# KickerBoard.net
KiCad netlist of a schematic drawn in EAGLE
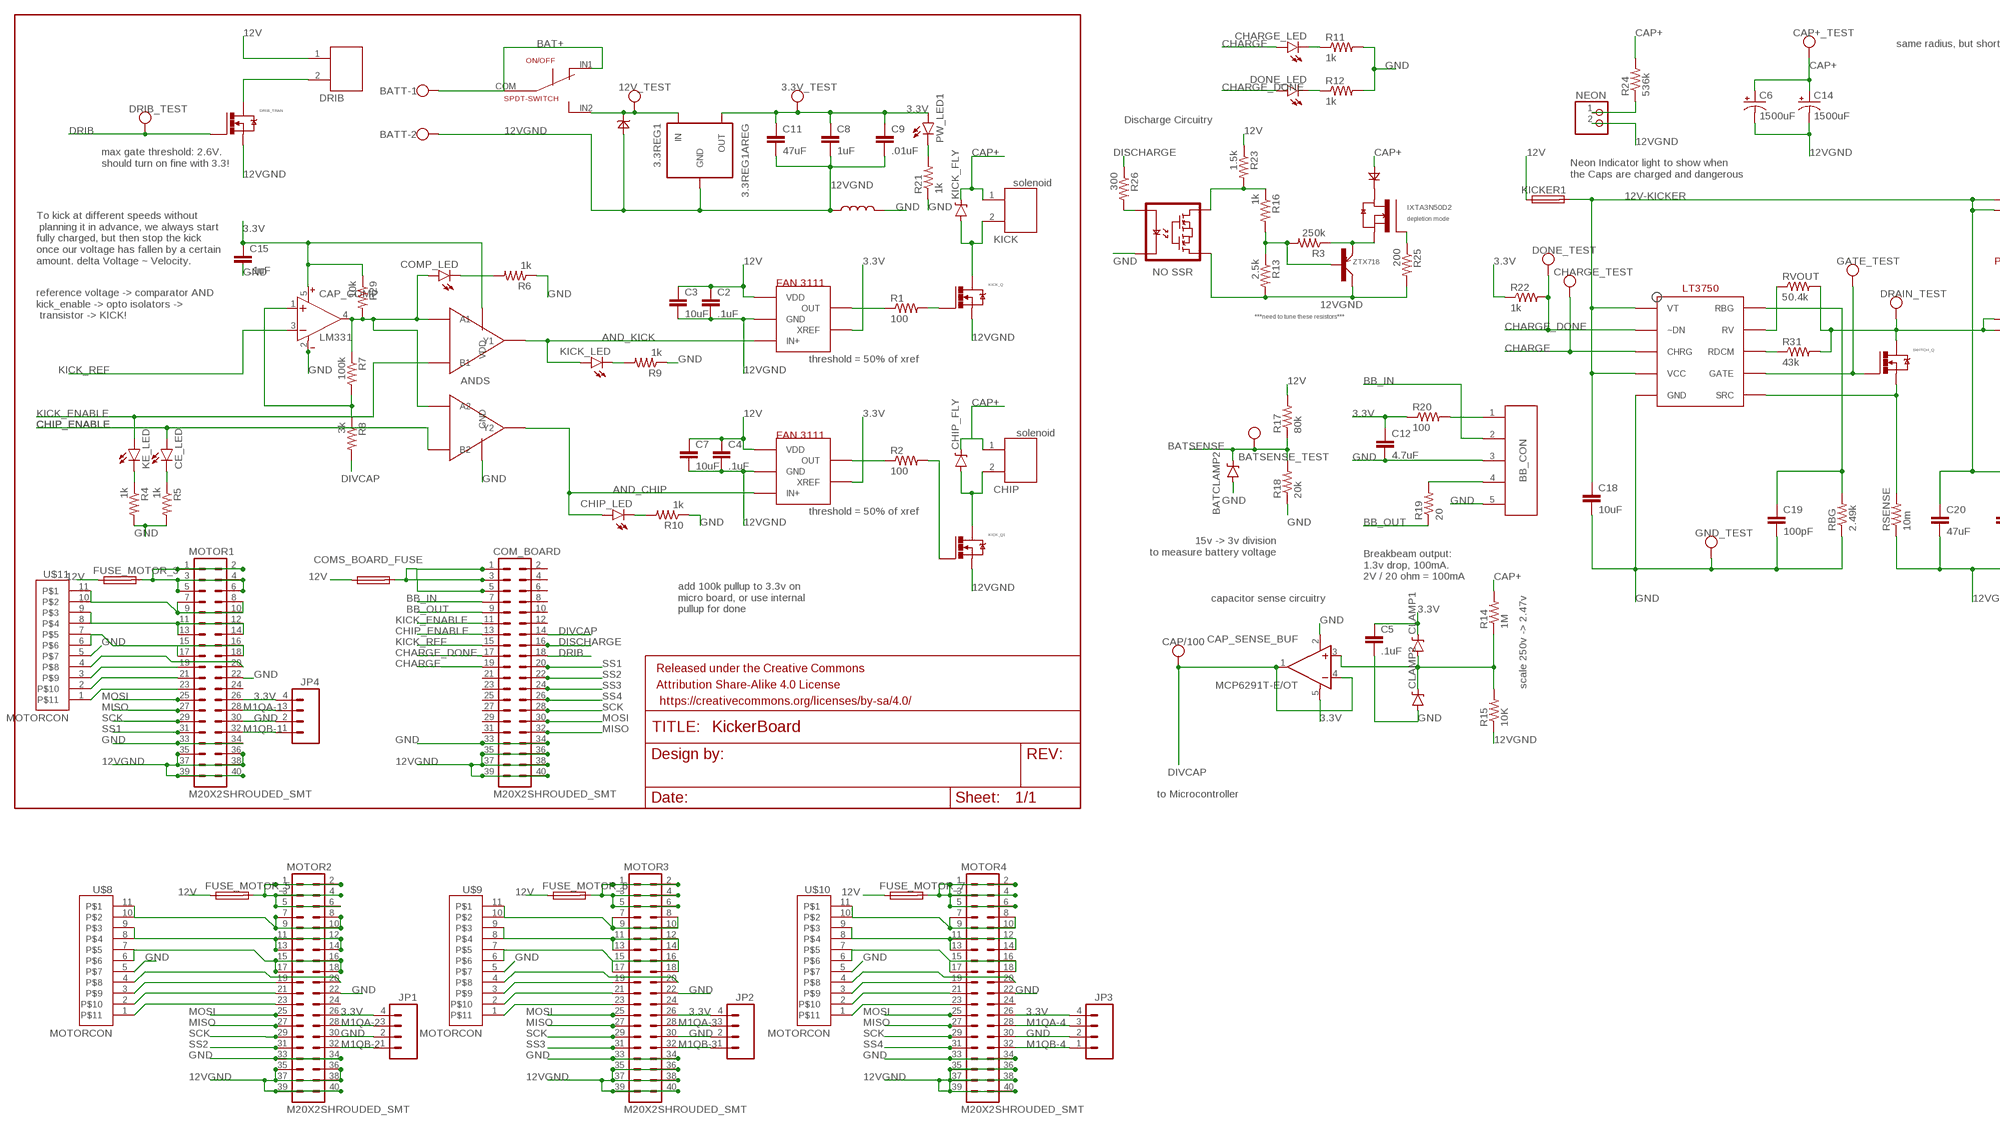
[diagram p0: schematic, sheet 1, part 1 of 3]
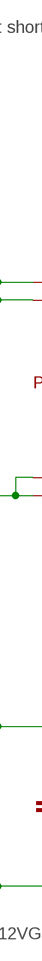
[diagram p1: schematic, sheet 1, part 2 of 3]
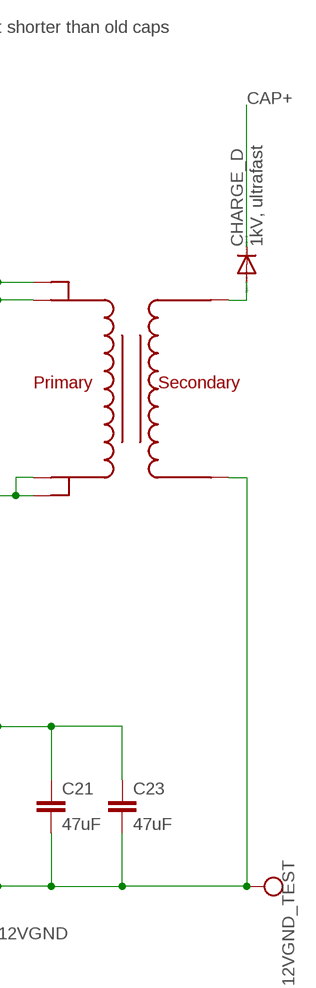
[diagram p2: schematic, sheet 1, part 3 of 3]

(export (version "E")
  (design (tool "Eeschema 10.0.6"))
  (components
    (comp (ref "3.3REG1")
      (value "3.3REG1AREG")
      (footprint "eagle-import:DPAK")
      (libsource (lib "eagle-import") (part "3.3REG1AREG"))
    )
    (comp (ref "3.3V_TEST")
      (value "TEST_PT")
      (footprint "eagle-import:TESTING_PT")
      (libsource (lib "eagle-import") (part "TEST_PT"))
    )
    (comp (ref "12VGND_TEST")
      (value "TEST_PT")
      (footprint "eagle-import:TESTING_PT")
      (libsource (lib "eagle-import") (part "TEST_PT"))
    )
    (comp (ref "12V_TEST")
      (value "TEST_PT")
      (footprint "eagle-import:TESTING_PT")
      (libsource (lib "eagle-import") (part "TEST_PT"))
    )
    (comp (ref "ANDS")
      (value "AND-DUAL")
      (footprint "eagle-import:TSSOP8")
      (libsource (lib "eagle-import") (part "AND-DUAL"))
    )
    (comp (ref "BATCLAMP2")
      (value "DIODE-ZENERDO214AC")
      (footprint "eagle-import:DO214AC")
      (libsource (lib "eagle-import") (part "DIODE-ZENERDO214AC"))
    )
    (comp (ref "BATSENSE_TEST")
      (value "TEST_PT")
      (footprint "eagle-import:TESTING_PT")
      (libsource (lib "eagle-import") (part "TEST_PT"))
    )
    (comp (ref "BATT")
      (value "W237-102")
      (footprint "eagle-import:W237-102")
      (fields (field (name "MPN") "237-102"))
      (libsource (lib "eagle-import") (part "W237-102"))
    )
    (comp (ref "BB_CON")
      (value "JST-5")
      (footprint "eagle-import:JST-5-2MM")
      (libsource (lib "eagle-import") (part "JST-5"))
    )
    (comp (ref "C2")
      (value ".1uF")
      (footprint "eagle-import:1206")
      (libsource (lib "eagle-import") (part "CAP1206"))
    )
    (comp (ref "C3")
      (value "10uF")
      (footprint "eagle-import:1206")
      (libsource (lib "eagle-import") (part "CAP1206"))
    )
    (comp (ref "C4")
      (value ".1uF")
      (footprint "eagle-import:1206")
      (libsource (lib "eagle-import") (part "CAP1206"))
    )
    (comp (ref "C5")
      (value ".1uF")
      (footprint "eagle-import:0805")
      (libsource (lib "eagle-import") (part "CAP0805"))
    )
    (comp (ref "C6")
      (value "1500uF")
      (footprint "eagle-import:EB35D")
      (libsource (lib "eagle-import") (part "CPOL-USE10-35"))
    )
    (comp (ref "C7")
      (value "10uF")
      (footprint "eagle-import:1206")
      (libsource (lib "eagle-import") (part "CAP1206"))
    )
    (comp (ref "C8")
      (value "1uF")
      (footprint "eagle-import:0805")
      (libsource (lib "eagle-import") (part "CAP0805"))
    )
    (comp (ref "C9")
      (value ".01uF")
      (footprint "eagle-import:0805")
      (libsource (lib "eagle-import") (part "CAP0805"))
    )
    (comp (ref "C11")
      (value "47uF")
      (footprint "eagle-import:1206")
      (libsource (lib "eagle-import") (part "CAP1206"))
    )
    (comp (ref "C12")
      (value "4.7uF")
      (footprint "eagle-import:0805")
      (libsource (lib "eagle-import") (part "CAP0805"))
    )
    (comp (ref "C14")
      (value "1500uF")
      (footprint "eagle-import:EB35D")
      (libsource (lib "eagle-import") (part "CPOL-USE10-35"))
    )
    (comp (ref "C15")
      (value ".1uF")
      (footprint "eagle-import:0805")
      (libsource (lib "eagle-import") (part "CAP0805"))
    )
    (comp (ref "C18")
      (value "10uF")
      (footprint "eagle-import:0805")
      (libsource (lib "eagle-import") (part "CAP0805"))
    )
    (comp (ref "C19")
      (value "100pF")
      (footprint "eagle-import:0805")
      (libsource (lib "eagle-import") (part "CAP0805"))
    )
    (comp (ref "C20")
      (value "47uF")
      (footprint "eagle-import:1206")
      (libsource (lib "eagle-import") (part "CAP1206"))
    )
    (comp (ref "C21")
      (value "47uF")
      (footprint "eagle-import:1206")
      (libsource (lib "eagle-import") (part "CAP1206"))
    )
    (comp (ref "C23")
      (value "47uF")
      (footprint "eagle-import:1206")
      (libsource (lib "eagle-import") (part "CAP1206"))
    )
    (comp (ref "CAP+_TEST")
      (value "TEST_PT")
      (footprint "eagle-import:TESTING_PT")
      (libsource (lib "eagle-import") (part "TEST_PT"))
    )
    (comp (ref "CAP/100")
      (value "TEST_PT")
      (footprint "eagle-import:TESTING_PT")
      (libsource (lib "eagle-import") (part "TEST_PT"))
    )
    (comp (ref "CAP_COMP")
      (value "LM331")
      (footprint "eagle-import:SOT23-5")
      (libsource (lib "eagle-import") (part "LM331"))
    )
    (comp (ref "CAP_SENSE_BUF")
      (value "MCP6291T-E/OT")
      (footprint "eagle-import:SOT23-5")
      (libsource (lib "eagle-import") (part "MCP6291T-E/OT"))
    )
    (comp (ref "CE_LED")
      (value "LED1206")
      (footprint "eagle-import:LED-1206")
      (libsource (lib "eagle-import") (part "LED1206"))
    )
    (comp (ref "CHARGE_D")
      (value "1kV, ultrafast")
      (footprint "eagle-import:DO214AC")
      (libsource (lib "eagle-import") (part "DIODE-DO214AC"))
    )
    (comp (ref "CHARGE_LED")
      (value "LED1206")
      (footprint "eagle-import:LED-1206")
      (libsource (lib "eagle-import") (part "LED1206"))
    )
    (comp (ref "CHARGE_TEST")
      (value "TEST_PT")
      (footprint "eagle-import:TESTING_PT")
      (libsource (lib "eagle-import") (part "TEST_PT"))
    )
    (comp (ref "CHARGE_U")
      (value "LT3750")
      (footprint "eagle-import:10-MSOP")
      (libsource (lib "eagle-import") (part "LT3750"))
    )
    (comp (ref "CHIP")
      (value "JST-22MM")
      (footprint "eagle-import:JST-2-2MM")
      (libsource (lib "eagle-import") (part "JST-22MM"))
    )
    (comp (ref "CHIP_FLY")
      (value "DIODE-ZENERDO214AB")
      (footprint "eagle-import:DO214AB")
      (libsource (lib "eagle-import") (part "DIODE-ZENERDO214AB"))
    )
    (comp (ref "CHIP_LED")
      (value "LED1206")
      (footprint "eagle-import:LED-1206")
      (libsource (lib "eagle-import") (part "LED1206"))
    )
    (comp (ref "CLAMP1")
      (value "DIODE-ZENERDO214AC")
      (footprint "eagle-import:DO214AC")
      (libsource (lib "eagle-import") (part "DIODE-ZENERDO214AC"))
    )
    (comp (ref "CLAMP2")
      (value "DIODE-ZENERDO214AC")
      (footprint "eagle-import:DO214AC")
      (libsource (lib "eagle-import") (part "DIODE-ZENERDO214AC"))
    )
    (comp (ref "COMP_LED")
      (value "LED1206")
      (footprint "eagle-import:LED-1206")
      (libsource (lib "eagle-import") (part "LED1206"))
    )
    (comp (ref "COMS_BOARD_FUSE")
      (value "TR5")
      (footprint "eagle-import:TR5")
      (libsource (lib "eagle-import") (part "TR5"))
    )
    (comp (ref "COM_BOARD")
      (value "M20X2SHROUDED_SMT")
      (footprint "eagle-import:2X20_SHROUDED_SMT")
      (libsource (lib "eagle-import") (part "M20X2SHROUDED_SMT"))
    )
    (comp (ref "DONE_LED")
      (value "LED1206")
      (footprint "eagle-import:LED-1206")
      (libsource (lib "eagle-import") (part "LED1206"))
    )
    (comp (ref "DONE_TEST")
      (value "TEST_PT")
      (footprint "eagle-import:TESTING_PT")
      (libsource (lib "eagle-import") (part "TEST_PT"))
    )
    (comp (ref "DRAIN_TEST")
      (value "TEST_PT")
      (footprint "eagle-import:TESTING_PT")
      (libsource (lib "eagle-import") (part "TEST_PT"))
    )
    (comp (ref "DRIB")
      (value "JST-22MM")
      (footprint "eagle-import:JST-2-2MM")
      (libsource (lib "eagle-import") (part "JST-22MM"))
    )
    (comp (ref "DRIB_TEST")
      (value "TEST_PT")
      (footprint "eagle-import:TESTING_PT")
      (libsource (lib "eagle-import") (part "TEST_PT"))
    )
    (comp (ref "DRIB_TRAN")
      (value "N-MOSFETDPAK")
      (footprint "eagle-import:DPAK")
      (libsource (lib "eagle-import") (part "N-MOSFETDPAK"))
    )
    (comp (ref "FRAME4")
      (value "FRAME-LETTER")
      (footprint "eagle-import:CREATIVE_COMMONS")
      (libsource (lib "eagle-import") (part "FRAME-LETTER"))
    )
    (comp (ref "FUSE_MOTOR_3")
      (value "TR5")
      (footprint "eagle-import:TR5")
      (libsource (lib "eagle-import") (part "TR5"))
    )
    (comp (ref "FUSE_MOTOR_5")
      (value "TR5")
      (footprint "eagle-import:TR5")
      (libsource (lib "eagle-import") (part "TR5"))
    )
    (comp (ref "FUSE_MOTOR_6")
      (value "TR5")
      (footprint "eagle-import:TR5")
      (libsource (lib "eagle-import") (part "TR5"))
    )
    (comp (ref "FUSE_MOTOR_7")
      (value "TR5")
      (footprint "eagle-import:TR5")
      (libsource (lib "eagle-import") (part "TR5"))
    )
    (comp (ref "GATE_TEST")
      (value "TEST_PT")
      (footprint "eagle-import:TESTING_PT")
      (libsource (lib "eagle-import") (part "TEST_PT"))
    )
    (comp (ref "GND_TEST")
      (value "TEST_PT")
      (footprint "eagle-import:TESTING_PT")
      (libsource (lib "eagle-import") (part "TEST_PT"))
    )
    (comp (ref "JP1")
      (value "M04SMD_RA_FEMALE")
      (footprint "eagle-import:1X04_SMD_RA_FEMALE")
      (libsource (lib "eagle-import") (part "M04SMD_RA_FEMALE"))
    )
    (comp (ref "JP2")
      (value "M04SMD_RA_FEMALE")
      (footprint "eagle-import:1X04_SMD_RA_FEMALE")
      (libsource (lib "eagle-import") (part "M04SMD_RA_FEMALE"))
    )
    (comp (ref "JP3")
      (value "M04SMD_RA_FEMALE")
      (footprint "eagle-import:1X04_SMD_RA_FEMALE")
      (libsource (lib "eagle-import") (part "M04SMD_RA_FEMALE"))
    )
    (comp (ref "JP4")
      (value "M04SMD_RA_FEMALE")
      (footprint "eagle-import:1X04_SMD_RA_FEMALE")
      (libsource (lib "eagle-import") (part "M04SMD_RA_FEMALE"))
    )
    (comp (ref "KE_LED")
      (value "LED1206")
      (footprint "eagle-import:LED-1206")
      (libsource (lib "eagle-import") (part "LED1206"))
    )
    (comp (ref "KICK")
      (value "JST-22MM")
      (footprint "eagle-import:JST-2-2MM")
      (libsource (lib "eagle-import") (part "JST-22MM"))
    )
    (comp (ref "KICKER1")
      (value "TR5")
      (footprint "eagle-import:TR5")
      (libsource (lib "eagle-import") (part "TR5"))
    )
    (comp (ref "KICK_FLY")
      (value "DIODE-ZENERDO214AB")
      (footprint "eagle-import:DO214AB")
      (libsource (lib "eagle-import") (part "DIODE-ZENERDO214AB"))
    )
    (comp (ref "KICK_LED")
      (value "LED1206")
      (footprint "eagle-import:LED-1206")
      (libsource (lib "eagle-import") (part "LED1206"))
    )
    (comp (ref "KICK_Q")
      (value "N-MOSFETDPAK")
      (footprint "eagle-import:DPAK")
      (libsource (lib "eagle-import") (part "N-MOSFETDPAK"))
    )
    (comp (ref "KICK_Q1")
      (value "N-MOSFETDPAK")
      (footprint "eagle-import:DPAK")
      (libsource (lib "eagle-import") (part "N-MOSFETDPAK"))
    )
    (comp (ref "MOTOR1")
      (value "M20X2SHROUDED_SMT")
      (footprint "eagle-import:2X20_SHROUDED_SMT")
      (libsource (lib "eagle-import") (part "M20X2SHROUDED_SMT"))
    )
    (comp (ref "MOTOR2")
      (value "M20X2SHROUDED_SMT")
      (footprint "eagle-import:2X20_SHROUDED_SMT")
      (libsource (lib "eagle-import") (part "M20X2SHROUDED_SMT"))
    )
    (comp (ref "MOTOR3")
      (value "M20X2SHROUDED_SMT")
      (footprint "eagle-import:2X20_SHROUDED_SMT")
      (libsource (lib "eagle-import") (part "M20X2SHROUDED_SMT"))
    )
    (comp (ref "MOTOR4")
      (value "M20X2SHROUDED_SMT")
      (footprint "eagle-import:2X20_SHROUDED_SMT")
      (libsource (lib "eagle-import") (part "M20X2SHROUDED_SMT"))
    )
    (comp (ref "NEON")
      (value "PINHD-1X2")
      (footprint "eagle-import:1X02")
      (libsource (lib "eagle-import") (part "PINHD-1X2"))
    )
    (comp (ref "ON/OFF")
      (value "SPDT-SWITCH")
      (footprint "eagle-import:CK_SWITCH")
      (libsource (lib "eagle-import") (part "SPDT-SWITCH"))
    )
    (comp (ref "PW_LED1")
      (value "LED1206")
      (footprint "eagle-import:LED-1206")
      (libsource (lib "eagle-import") (part "LED1206"))
    )
    (comp (ref "R1")
      (value "100")
      (footprint "eagle-import:0805")
      (libsource (lib "eagle-import") (part "SparkFun-Resistors_RESISTOR0805-RES"))
    )
    (comp (ref "R2")
      (value "100")
      (footprint "eagle-import:0805")
      (libsource (lib "eagle-import") (part "SparkFun-Resistors_RESISTOR0805-RES"))
    )
    (comp (ref "R3")
      (value "250k")
      (footprint "eagle-import:0805")
      (libsource (lib "eagle-import") (part "RESISTOR0805-RES"))
    )
    (comp (ref "R4")
      (value "1k")
      (footprint "eagle-import:0805")
      (libsource (lib "eagle-import") (part "RESISTOR0805-RES"))
    )
    (comp (ref "R5")
      (value "1k")
      (footprint "eagle-import:0805")
      (libsource (lib "eagle-import") (part "RESISTOR0805-RES"))
    )
    (comp (ref "R6")
      (value "1k")
      (footprint "eagle-import:0805")
      (libsource (lib "eagle-import") (part "RESISTOR0805-RES"))
    )
    (comp (ref "R7")
      (value "100k")
      (footprint "eagle-import:0805")
      (libsource (lib "eagle-import") (part "RESISTOR0805-RES"))
    )
    (comp (ref "R8")
      (value "3k")
      (footprint "eagle-import:0805")
      (libsource (lib "eagle-import") (part "RESISTOR0805-RES"))
    )
    (comp (ref "R9")
      (value "1k")
      (footprint "eagle-import:0805")
      (libsource (lib "eagle-import") (part "RESISTOR0805-RES"))
    )
    (comp (ref "R10")
      (value "1k")
      (footprint "eagle-import:0805")
      (libsource (lib "eagle-import") (part "RESISTOR0805-RES"))
    )
    (comp (ref "R11")
      (value "1k")
      (footprint "eagle-import:0805")
      (libsource (lib "eagle-import") (part "RESISTOR0805-RES"))
    )
    (comp (ref "R12")
      (value "1k")
      (footprint "eagle-import:0805")
      (libsource (lib "eagle-import") (part "RESISTOR0805-RES"))
    )
    (comp (ref "R13")
      (value "2.5k")
      (footprint "eagle-import:0805")
      (libsource (lib "eagle-import") (part "RESISTOR0805-RES"))
    )
    (comp (ref "R14")
      (value "1M")
      (footprint "eagle-import:0805")
      (libsource (lib "eagle-import") (part "SparkFun-Resistors_RESISTOR0805-RES"))
    )
    (comp (ref "R15")
      (value "10K")
      (footprint "eagle-import:0805")
      (libsource (lib "eagle-import") (part "SparkFun-Resistors_RESISTOR0805-RES"))
    )
    (comp (ref "R16")
      (value "1k")
      (footprint "eagle-import:0805")
      (libsource (lib "eagle-import") (part "RESISTOR0805-RES"))
    )
    (comp (ref "R17")
      (value "80k")
      (footprint "eagle-import:0805")
      (libsource (lib "eagle-import") (part "RESISTOR0805-RES"))
    )
    (comp (ref "R18")
      (value "20k")
      (footprint "eagle-import:0805")
      (libsource (lib "eagle-import") (part "RESISTOR0805-RES"))
    )
    (comp (ref "R19")
      (value "20")
      (footprint "eagle-import:0805")
      (libsource (lib "eagle-import") (part "RESISTOR0805-RES"))
    )
    (comp (ref "R20")
      (value "100")
      (footprint "eagle-import:0805")
      (libsource (lib "eagle-import") (part "RESISTOR0805-RES"))
    )
    (comp (ref "R21")
      (value "1k")
      (footprint "eagle-import:0805")
      (libsource (lib "eagle-import") (part "RESISTOR0805-RES"))
    )
    (comp (ref "R22")
      (value "1k")
      (footprint "eagle-import:0805")
      (libsource (lib "eagle-import") (part "RESISTOR0805-RES"))
    )
    (comp (ref "R23")
      (value "1.5k")
      (footprint "eagle-import:0805")
      (libsource (lib "eagle-import") (part "RESISTOR0805-RES"))
    )
    (comp (ref "R24")
      (value "536k")
      (footprint "eagle-import:0805")
      (libsource (lib "eagle-import") (part "RESISTOR0805-RES"))
    )
    (comp (ref "R25")
      (value "200")
      (footprint "eagle-import:0805")
      (libsource (lib "eagle-import") (part "RESISTOR0805-RES"))
    )
    (comp (ref "R26")
      (value "300")
      (footprint "eagle-import:0805")
      (libsource (lib "eagle-import") (part "RESISTOR0805-RES"))
    )
    (comp (ref "R29")
      (value "10k")
      (footprint "eagle-import:0805")
      (libsource (lib "eagle-import") (part "RESISTOR0805-RES"))
    )
    (comp (ref "R31")
      (value "43k")
      (footprint "eagle-import:0805")
      (libsource (lib "eagle-import") (part "RESISTOR0805-RES"))
    )
    (comp (ref "RBG")
      (value "2.49k")
      (footprint "eagle-import:0805")
      (libsource (lib "eagle-import") (part "RESISTOR0805-RES"))
    )
    (comp (ref "RSENSE")
      (value "10m")
      (footprint "eagle-import:R2512")
      (libsource (lib "eagle-import") (part "RESISTOR2512"))
    )
    (comp (ref "RVOUT")
      (value "50.4k")
      (footprint "eagle-import:0805")
      (libsource (lib "eagle-import") (part "RESISTOR0805-RES"))
    )
    (comp (ref "SWITCH_Q")
      (value "N-MOSFETDPAK")
      (footprint "eagle-import:DPAK")
      (libsource (lib "eagle-import") (part "N-MOSFETDPAK"))
    )
    (comp (ref "U$1")
      (value "FAN31111")
      (footprint "eagle-import:SOT23-5")
      (libsource (lib "eagle-import") (part "FAN31111"))
    )
    (comp (ref "U$2")
      (value "IXTA3N50D2")
      (footprint "eagle-import:TO-263")
      (libsource (lib "eagle-import") (part "IXTA3N50D2"))
    )
    (comp (ref "U$3")
      (value "32052-TRANSFORMER")
      (footprint "eagle-import:10-TRANSFORMER")
      (libsource (lib "eagle-import") (part "32052-TRANSFORMER"))
    )
    (comp (ref "U$4")
      (value "FAN31111")
      (footprint "eagle-import:SOT23-5")
      (libsource (lib "eagle-import") (part "FAN31111"))
    )
    (comp (ref "U$5")
      (value "VO1400AEFTR")
      (footprint "eagle-import:SOP4")
      (libsource (lib "eagle-import") (part "VO1400AEFTR"))
    )
    (comp (ref "U$6")
      (value "ZTX718")
      (footprint "eagle-import:TO92")
      (libsource (lib "eagle-import") (part "ZTX718"))
    )
    (comp (ref "U$7")
      (value "1N4007")
      (footprint "eagle-import:THROUGH-HOLE-2")
      (libsource (lib "eagle-import") (part "1N4007"))
    )
    (comp (ref "U$8")
      (value "MOTORCON")
      (footprint "eagle-import:GEN3CON")
      (libsource (lib "eagle-import") (part "MOTORCON"))
    )
    (comp (ref "U$9")
      (value "MOTORCON")
      (footprint "eagle-import:GEN3CON")
      (libsource (lib "eagle-import") (part "MOTORCON"))
    )
    (comp (ref "U$10")
      (value "MOTORCON")
      (footprint "eagle-import:GEN3CON")
      (libsource (lib "eagle-import") (part "MOTORCON"))
    )
    (comp (ref "U$11")
      (value "MOTORCON")
      (footprint "eagle-import:GEN3CON")
      (libsource (lib "eagle-import") (part "MOTORCON"))
    )
    (comp (ref "U$12")
      (value "13VZENER")
      (footprint "eagle-import:THROUGH-HOLE-2")
      (libsource (lib "eagle-import") (part "13VZENER"))
    )
    (comp (ref "U$13")
      (value "INDUCTOR")
      (footprint "eagle-import:0805")
      (libsource (lib "eagle-import") (part "INDUCTOR"))
    )
  )
  (nets
    (net (code "1") (name "/3.3V") (class "Default")
      (node (ref "3.3REG1") (pin "SOURCE") (pinfunction "OUT_SOURCE") (pintype "bidirectional"))
      (node (ref "3.3V_TEST") (pin "P$1") (pinfunction "P$1_P$1") (pintype "bidirectional"))
      (node (ref "ANDS") (pin "P$8") (pinfunction "VDD_P$8") (pintype "bidirectional"))
      (node (ref "C11") (pin "1") (pinfunction "1_1") (pintype "passive"))
      (node (ref "C12") (pin "1") (pinfunction "1_1") (pintype "passive"))
      (node (ref "C15") (pin "1") (pinfunction "1_1") (pintype "passive"))
      (node (ref "C5") (pin "1") (pinfunction "1_1") (pintype "passive"))
      (node (ref "C8") (pin "1") (pinfunction "1_1") (pintype "passive"))
      (node (ref "C9") (pin "1") (pinfunction "1_1") (pintype "passive"))
      (node (ref "CAP_COMP") (pin "5") (pinfunction "V+_5") (pintype "power_in"))
      (node (ref "CAP_SENSE_BUF") (pin "5") (pinfunction "V+_5") (pintype "power_in"))
      (node (ref "CLAMP1") (pin "C") (pinfunction "C_C") (pintype "passive"))
      (node (ref "JP1") (pin "4") (pinfunction "4_4") (pintype "passive"))
      (node (ref "JP2") (pin "4") (pinfunction "4_4") (pintype "passive"))
      (node (ref "JP3") (pin "4") (pinfunction "4_4") (pintype "passive"))
      (node (ref "JP4") (pin "4") (pinfunction "4_4") (pintype "passive"))
      (node (ref "MOTOR1") (pin "26") (pinfunction "26_26") (pintype "passive"))
      (node (ref "MOTOR2") (pin "26") (pinfunction "26_26") (pintype "passive"))
      (node (ref "MOTOR3") (pin "26") (pinfunction "26_26") (pintype "passive"))
      (node (ref "MOTOR4") (pin "26") (pinfunction "26_26") (pintype "passive"))
      (node (ref "PW_LED1") (pin "A") (pinfunction "A_A") (pintype "passive"))
      (node (ref "R20") (pin "1") (pinfunction "1_1") (pintype "passive"))
      (node (ref "R22") (pin "1") (pinfunction "1_1") (pintype "passive"))
      (node (ref "R29") (pin "1") (pinfunction "1_1") (pintype "passive"))
      (node (ref "U$1") (pin "4") (pinfunction "XREF_4") (pintype "input"))
      (node (ref "U$4") (pin "4") (pinfunction "XREF_4") (pintype "input"))
    )
    (net (code "2") (name "/12V") (class "Default")
      (node (ref "12V_TEST") (pin "P$1") (pinfunction "P$1_P$1") (pintype "bidirectional"))
      (node (ref "3.3REG1") (pin "GATE") (pinfunction "IN_GATE") (pintype "input"))
      (node (ref "C2") (pin "1") (pinfunction "1_1") (pintype "passive"))
      (node (ref "C3") (pin "1") (pinfunction "1_1") (pintype "passive"))
      (node (ref "C4") (pin "1") (pinfunction "1_1") (pintype "passive"))
      (node (ref "C7") (pin "1") (pinfunction "1_1") (pintype "passive"))
      (node (ref "COMS_BOARD_FUSE") (pin "1") (pinfunction "1_1") (pintype "passive"))
      (node (ref "DRIB") (pin "1") (pinfunction "P$1_1") (pintype "bidirectional"))
      (node (ref "FUSE_MOTOR_3") (pin "1") (pinfunction "1_1") (pintype "passive"))
      (node (ref "FUSE_MOTOR_5") (pin "1") (pinfunction "1_1") (pintype "passive"))
      (node (ref "FUSE_MOTOR_6") (pin "1") (pinfunction "1_1") (pintype "passive"))
      (node (ref "FUSE_MOTOR_7") (pin "1") (pinfunction "1_1") (pintype "passive"))
      (node (ref "KICKER1") (pin "1") (pinfunction "1_1") (pintype "passive"))
      (node (ref "ON/OFF") (pin "IN2") (pinfunction "P2_IN2") (pintype "bidirectional"))
      (node (ref "R17") (pin "2") (pinfunction "2_2") (pintype "passive"))
      (node (ref "R23") (pin "1") (pinfunction "1_1") (pintype "passive"))
      (node (ref "U$1") (pin "1") (pinfunction "VDD_1") (pintype "power_in"))
      (node (ref "U$12") (pin "-") (pinfunction "-_-") (pintype "bidirectional"))
      (node (ref "U$4") (pin "1") (pinfunction "VDD_1") (pintype "power_in"))
    )
    (net (code "3") (name "/12V-KICKER") (class "Default")
      (node (ref "C18") (pin "1") (pinfunction "1_1") (pintype "passive"))
      (node (ref "C20") (pin "1") (pinfunction "1_1") (pintype "passive"))
      (node (ref "C21") (pin "1") (pinfunction "1_1") (pintype "passive"))
      (node (ref "C23") (pin "1") (pinfunction "1_1") (pintype "passive"))
      (node (ref "CHARGE_U") (pin "P$1") (pinfunction "VT_P$1") (pintype "bidirectional"))
      (node (ref "CHARGE_U") (pin "P$4") (pinfunction "VCC_P$4") (pintype "bidirectional"))
      (node (ref "KICKER1") (pin "2") (pinfunction "2_2") (pintype "passive"))
      (node (ref "U$3") (pin "P$4") (pinfunction "P$4_P$4") (pintype "bidirectional"))
      (node (ref "U$3") (pin "P$5") (pinfunction "P$5_P$5") (pintype "bidirectional"))
    )
    (net (code "4") (name "/12VGND") (class "Default")
      (node (ref "12VGND_TEST") (pin "P$1") (pinfunction "P$1_P$1") (pintype "bidirectional"))
      (node (ref "3.3REG1") (pin "DRAIN") (pinfunction "GND_DRAIN") (pintype "bidirectional"))
      (node (ref "BATT") (pin "2") (pinfunction "KL_2") (pintype "passive"))
      (node (ref "C11") (pin "2") (pinfunction "2_2") (pintype "passive"))
      (node (ref "C14") (pin "-") (pinfunction "-_-") (pintype "passive"))
      (node (ref "C2") (pin "2") (pinfunction "2_2") (pintype "passive"))
      (node (ref "C20") (pin "2") (pinfunction "2_2") (pintype "passive"))
      (node (ref "C21") (pin "2") (pinfunction "2_2") (pintype "passive"))
      (node (ref "C23") (pin "2") (pinfunction "2_2") (pintype "passive"))
      (node (ref "C3") (pin "2") (pinfunction "2_2") (pintype "passive"))
      (node (ref "C4") (pin "2") (pinfunction "2_2") (pintype "passive"))
      (node (ref "C6") (pin "-") (pinfunction "-_-") (pintype "passive"))
      (node (ref "C7") (pin "2") (pinfunction "2_2") (pintype "passive"))
      (node (ref "C8") (pin "2") (pinfunction "2_2") (pintype "passive"))
      (node (ref "C9") (pin "2") (pinfunction "2_2") (pintype "passive"))
      (node (ref "COM_BOARD") (pin "35") (pinfunction "35_35") (pintype "passive"))
      (node (ref "COM_BOARD") (pin "36") (pinfunction "36_36") (pintype "passive"))
      (node (ref "COM_BOARD") (pin "37") (pinfunction "37_37") (pintype "passive"))
      (node (ref "COM_BOARD") (pin "38") (pinfunction "38_38") (pintype "passive"))
      (node (ref "COM_BOARD") (pin "39") (pinfunction "39_39") (pintype "passive"))
      (node (ref "COM_BOARD") (pin "40") (pinfunction "40_40") (pintype "passive"))
      (node (ref "DRIB_TRAN") (pin "SOURCE") (pinfunction "S_SOURCE") (pintype "bidirectional"))
      (node (ref "KICK_Q") (pin "SOURCE") (pinfunction "S_SOURCE") (pintype "bidirectional"))
      (node (ref "KICK_Q1") (pin "SOURCE") (pinfunction "S_SOURCE") (pintype "bidirectional"))
      (node (ref "MOTOR1") (pin "35") (pinfunction "35_35") (pintype "passive"))
      (node (ref "MOTOR1") (pin "36") (pinfunction "36_36") (pintype "passive"))
      (node (ref "MOTOR1") (pin "37") (pinfunction "37_37") (pintype "passive"))
      (node (ref "MOTOR1") (pin "38") (pinfunction "38_38") (pintype "passive"))
      (node (ref "MOTOR1") (pin "39") (pinfunction "39_39") (pintype "passive"))
      (node (ref "MOTOR1") (pin "40") (pinfunction "40_40") (pintype "passive"))
      (node (ref "MOTOR2") (pin "35") (pinfunction "35_35") (pintype "passive"))
      (node (ref "MOTOR2") (pin "36") (pinfunction "36_36") (pintype "passive"))
      (node (ref "MOTOR2") (pin "37") (pinfunction "37_37") (pintype "passive"))
      (node (ref "MOTOR2") (pin "38") (pinfunction "38_38") (pintype "passive"))
      (node (ref "MOTOR2") (pin "39") (pinfunction "39_39") (pintype "passive"))
      (node (ref "MOTOR2") (pin "40") (pinfunction "40_40") (pintype "passive"))
      (node (ref "MOTOR3") (pin "35") (pinfunction "35_35") (pintype "passive"))
      (node (ref "MOTOR3") (pin "36") (pinfunction "36_36") (pintype "passive"))
      (node (ref "MOTOR3") (pin "37") (pinfunction "37_37") (pintype "passive"))
      (node (ref "MOTOR3") (pin "38") (pinfunction "38_38") (pintype "passive"))
      (node (ref "MOTOR3") (pin "39") (pinfunction "39_39") (pintype "passive"))
      (node (ref "MOTOR3") (pin "40") (pinfunction "40_40") (pintype "passive"))
      (node (ref "MOTOR4") (pin "35") (pinfunction "35_35") (pintype "passive"))
      (node (ref "MOTOR4") (pin "36") (pinfunction "36_36") (pintype "passive"))
      (node (ref "MOTOR4") (pin "37") (pinfunction "37_37") (pintype "passive"))
      (node (ref "MOTOR4") (pin "38") (pinfunction "38_38") (pintype "passive"))
      (node (ref "MOTOR4") (pin "39") (pinfunction "39_39") (pintype "passive"))
      (node (ref "MOTOR4") (pin "40") (pinfunction "40_40") (pintype "passive"))
      (node (ref "NEON") (pin "2") (pinfunction "2_2") (pintype "passive"))
      (node (ref "R13") (pin "2") (pinfunction "2_2") (pintype "passive"))
      (node (ref "R15") (pin "1") (pinfunction "1_1") (pintype "passive"))
      (node (ref "R25") (pin "2") (pinfunction "2_2") (pintype "passive"))
      (node (ref "RSENSE") (pin "1") (pinfunction "1_1") (pintype "passive"))
      (node (ref "U$1") (pin "2") (pinfunction "GND_2") (pintype "power_in"))
      (node (ref "U$12") (pin "+") (pinfunction "+_+") (pintype "bidirectional"))
      (node (ref "U$13") (pin "1") (pinfunction "P$1_1") (pintype "bidirectional"))
      (node (ref "U$3") (pin "P$10") (pinfunction "P$10_P$10") (pintype "bidirectional"))
      (node (ref "U$4") (pin "2") (pinfunction "GND_2") (pintype "power_in"))
      (node (ref "U$5") (pin "3") (pinfunction "S2_3") (pintype "bidirectional"))
      (node (ref "U$6") (pin "LEFT") (pinfunction "COLLECTOR_LEFT") (pintype "bidirectional"))
    )
    (net (code "5") (name "/AND_CHIP") (class "Default")
      (node (ref "ANDS") (pin "P$3") (pinfunction "Y2_P$3") (pintype "bidirectional"))
      (node (ref "CHIP_LED") (pin "A") (pinfunction "A_A") (pintype "passive"))
      (node (ref "U$1") (pin "3") (pinfunction "IN+_3") (pintype "input"))
    )
    (net (code "6") (name "/AND_KICK") (class "Default")
      (node (ref "ANDS") (pin "P$7") (pinfunction "Y1_P$7") (pintype "bidirectional"))
      (node (ref "KICK_LED") (pin "A") (pinfunction "A_A") (pintype "passive"))
      (node (ref "U$4") (pin "3") (pinfunction "IN+_3") (pintype "input"))
    )
    (net (code "7") (name "/BAT+") (class "Default")
      (node (ref "BATT") (pin "1") (pinfunction "KL_1") (pintype "passive"))
      (node (ref "ON/OFF") (pin "COM") (pinfunction "COM_COM") (pintype "bidirectional"))
      (node (ref "ON/OFF") (pin "IN1") (pinfunction "P1_IN1") (pintype "bidirectional"))
    )
    (net (code "8") (name "/BATSENSE") (class "Default")
      (node (ref "BATCLAMP2") (pin "C") (pinfunction "C_C") (pintype "passive"))
      (node (ref "BATSENSE_TEST") (pin "P$1") (pinfunction "P$1_P$1") (pintype "bidirectional"))
      (node (ref "R17") (pin "1") (pinfunction "1_1") (pintype "passive"))
      (node (ref "R18") (pin "2") (pinfunction "2_2") (pintype "passive"))
    )
    (net (code "9") (name "/BB_IN") (class "Default")
      (node (ref "BB_CON") (pin "2") (pinfunction "P$2_2") (pintype "bidirectional"))
      (node (ref "COM_BOARD") (pin "7") (pinfunction "7_7") (pintype "passive"))
    )
    (net (code "10") (name "/BB_OUT") (class "Default")
      (node (ref "COM_BOARD") (pin "9") (pinfunction "9_9") (pintype "passive"))
      (node (ref "R19") (pin "1") (pinfunction "1_1") (pintype "passive"))
    )
    (net (code "11") (name "/CAP+") (class "Default")
      (node (ref "C14") (pin "+") (pinfunction "+_+") (pintype "passive"))
      (node (ref "C6") (pin "+") (pinfunction "+_+") (pintype "passive"))
      (node (ref "CAP+_TEST") (pin "P$1") (pinfunction "P$1_P$1") (pintype "bidirectional"))
      (node (ref "CHARGE_D") (pin "C") (pinfunction "C_C") (pintype "passive"))
      (node (ref "CHIP") (pin "1") (pinfunction "P$1_1") (pintype "bidirectional"))
      (node (ref "CHIP_FLY") (pin "CATHODE") (pinfunction "C_CATHODE") (pintype "passive"))
      (node (ref "KICK") (pin "1") (pinfunction "P$1_1") (pintype "bidirectional"))
      (node (ref "KICK_FLY") (pin "CATHODE") (pinfunction "C_CATHODE") (pintype "passive"))
      (node (ref "R14") (pin "2") (pinfunction "2_2") (pintype "passive"))
      (node (ref "R24") (pin "2") (pinfunction "2_2") (pintype "passive"))
      (node (ref "U$7") (pin "+") (pinfunction "D+_+") (pintype "bidirectional"))
    )
    (net (code "12") (name "/CHARGE") (class "Default")
      (node (ref "CHARGE_LED") (pin "A") (pinfunction "A_A") (pintype "passive"))
      (node (ref "CHARGE_TEST") (pin "P$1") (pinfunction "P$1_P$1") (pintype "bidirectional"))
      (node (ref "CHARGE_U") (pin "P$3") (pinfunction "CHRG_P$3") (pintype "bidirectional"))
      (node (ref "COM_BOARD") (pin "19") (pinfunction "19_19") (pintype "passive"))
    )
    (net (code "13") (name "/CHARGE_DONE") (class "Default")
      (node (ref "CHARGE_U") (pin "P$2") (pinfunction "~{DN}_P$2") (pintype "bidirectional"))
      (node (ref "COM_BOARD") (pin "17") (pinfunction "17_17") (pintype "passive"))
      (node (ref "DONE_LED") (pin "A") (pinfunction "A_A") (pintype "passive"))
      (node (ref "DONE_TEST") (pin "P$1") (pinfunction "P$1_P$1") (pintype "bidirectional"))
      (node (ref "R22") (pin "2") (pinfunction "2_2") (pintype "passive"))
    )
    (net (code "14") (name "/CHIP_ENABLE") (class "Default")
      (node (ref "ANDS") (pin "P$6") (pinfunction "B2_P$6") (pintype "bidirectional"))
      (node (ref "CE_LED") (pin "A") (pinfunction "A_A") (pintype "passive"))
      (node (ref "COM_BOARD") (pin "13") (pinfunction "13_13") (pintype "passive"))
    )
    (net (code "15") (name "/DISCHARGE") (class "Default")
      (node (ref "COM_BOARD") (pin "16") (pinfunction "16_16") (pintype "passive"))
      (node (ref "R26") (pin "1") (pinfunction "1_1") (pintype "passive"))
    )
    (net (code "16") (name "/DIVCAP") (class "Default")
      (node (ref "CAP/100") (pin "P$1") (pinfunction "P$1_P$1") (pintype "bidirectional"))
      (node (ref "CAP_SENSE_BUF") (pin "1") (pinfunction "OUT_1") (pintype "output"))
      (node (ref "CAP_SENSE_BUF") (pin "4") (pinfunction "-IN_4") (pintype "input"))
      (node (ref "COM_BOARD") (pin "14") (pinfunction "14_14") (pintype "passive"))
      (node (ref "R8") (pin "2") (pinfunction "2_2") (pintype "passive"))
    )
    (net (code "17") (name "/DRIB") (class "Default")
      (node (ref "COM_BOARD") (pin "18") (pinfunction "18_18") (pintype "passive"))
      (node (ref "DRIB_TEST") (pin "P$1") (pinfunction "P$1_P$1") (pintype "bidirectional"))
      (node (ref "DRIB_TRAN") (pin "GATE") (pinfunction "G_GATE") (pintype "bidirectional"))
    )
    (net (code "18") (name "/GND") (class "Default")
      (node (ref "ANDS") (pin "P$4") (pinfunction "GND_P$4") (pintype "bidirectional"))
      (node (ref "BATCLAMP2") (pin "A") (pinfunction "A_A") (pintype "passive"))
      (node (ref "BB_CON") (pin "3") (pinfunction "P$3_3") (pintype "bidirectional"))
      (node (ref "BB_CON") (pin "5") (pinfunction "P$5_5") (pintype "bidirectional"))
      (node (ref "C12") (pin "2") (pinfunction "2_2") (pintype "passive"))
      (node (ref "C15") (pin "2") (pinfunction "2_2") (pintype "passive"))
      (node (ref "C18") (pin "2") (pinfunction "2_2") (pintype "passive"))
      (node (ref "C19") (pin "2") (pinfunction "2_2") (pintype "passive"))
      (node (ref "C5") (pin "2") (pinfunction "2_2") (pintype "passive"))
      (node (ref "CAP_COMP") (pin "2") (pinfunction "V-_2") (pintype "power_in"))
      (node (ref "CAP_SENSE_BUF") (pin "2") (pinfunction "V-_2") (pintype "power_in"))
      (node (ref "CHARGE_U") (pin "P$5") (pinfunction "GND_P$5") (pintype "bidirectional"))
      (node (ref "CLAMP2") (pin "A") (pinfunction "A_A") (pintype "passive"))
      (node (ref "COM_BOARD") (pin "33") (pinfunction "33_33") (pintype "passive"))
      (node (ref "COM_BOARD") (pin "34") (pinfunction "34_34") (pintype "passive"))
      (node (ref "GND_TEST") (pin "P$1") (pinfunction "P$1_P$1") (pintype "bidirectional"))
      (node (ref "JP1") (pin "2") (pinfunction "2_2") (pintype "passive"))
      (node (ref "JP2") (pin "2") (pinfunction "2_2") (pintype "passive"))
      (node (ref "JP3") (pin "2") (pinfunction "2_2") (pintype "passive"))
      (node (ref "JP4") (pin "2") (pinfunction "2_2") (pintype "passive"))
      (node (ref "MOTOR1") (pin "22") (pinfunction "22_22") (pintype "passive"))
      (node (ref "MOTOR1") (pin "30") (pinfunction "30_30") (pintype "passive"))
      (node (ref "MOTOR1") (pin "33") (pinfunction "33_33") (pintype "passive"))
      (node (ref "MOTOR1") (pin "34") (pinfunction "34_34") (pintype "passive"))
      (node (ref "MOTOR2") (pin "22") (pinfunction "22_22") (pintype "passive"))
      (node (ref "MOTOR2") (pin "30") (pinfunction "30_30") (pintype "passive"))
      (node (ref "MOTOR2") (pin "33") (pinfunction "33_33") (pintype "passive"))
      (node (ref "MOTOR2") (pin "34") (pinfunction "34_34") (pintype "passive"))
      (node (ref "MOTOR3") (pin "22") (pinfunction "22_22") (pintype "passive"))
      (node (ref "MOTOR3") (pin "30") (pinfunction "30_30") (pintype "passive"))
      (node (ref "MOTOR3") (pin "33") (pinfunction "33_33") (pintype "passive"))
      (node (ref "MOTOR3") (pin "34") (pinfunction "34_34") (pintype "passive"))
      (node (ref "MOTOR4") (pin "22") (pinfunction "22_22") (pintype "passive"))
      (node (ref "MOTOR4") (pin "30") (pinfunction "30_30") (pintype "passive"))
      (node (ref "MOTOR4") (pin "33") (pinfunction "33_33") (pintype "passive"))
      (node (ref "MOTOR4") (pin "34") (pinfunction "34_34") (pintype "passive"))
      (node (ref "R10") (pin "1") (pinfunction "1_1") (pintype "passive"))
      (node (ref "R11") (pin "2") (pinfunction "2_2") (pintype "passive"))
      (node (ref "R12") (pin "2") (pinfunction "2_2") (pintype "passive"))
      (node (ref "R18") (pin "1") (pinfunction "1_1") (pintype "passive"))
      (node (ref "R21") (pin "1") (pinfunction "1_1") (pintype "passive"))
      (node (ref "R4") (pin "2") (pinfunction "2_2") (pintype "passive"))
      (node (ref "R5") (pin "2") (pinfunction "2_2") (pintype "passive"))
      (node (ref "R6") (pin "1") (pinfunction "1_1") (pintype "passive"))
      (node (ref "R9") (pin "1") (pinfunction "1_1") (pintype "passive"))
      (node (ref "RBG") (pin "1") (pinfunction "1_1") (pintype "passive"))
      (node (ref "U$10") (pin "5") (pinfunction "P$7_5") (pintype "bidirectional"))
      (node (ref "U$11") (pin "5") (pinfunction "P$7_5") (pintype "bidirectional"))
      (node (ref "U$13") (pin "2") (pinfunction "P$2_2") (pintype "bidirectional"))
      (node (ref "U$5") (pin "2") (pinfunction "LED-_2") (pintype "bidirectional"))
      (node (ref "U$8") (pin "5") (pinfunction "P$7_5") (pintype "bidirectional"))
      (node (ref "U$9") (pin "5") (pinfunction "P$7_5") (pintype "bidirectional"))
    )
    (net (code "19") (name "/KICK_ENABLE") (class "Default")
      (node (ref "ANDS") (pin "P$2") (pinfunction "B1_P$2") (pintype "bidirectional"))
      (node (ref "COM_BOARD") (pin "11") (pinfunction "11_11") (pintype "passive"))
      (node (ref "KE_LED") (pin "A") (pinfunction "A_A") (pintype "passive"))
    )
    (net (code "20") (name "/KICK_REF") (class "Default")
      (node (ref "CAP_COMP") (pin "3") (pinfunction "IN-_3") (pintype "input"))
      (node (ref "COM_BOARD") (pin "15") (pinfunction "15_15") (pintype "passive"))
    )
    (net (code "21") (name "/M1QA-1") (class "Default")
      (node (ref "JP4") (pin "3") (pinfunction "3_3") (pintype "passive"))
      (node (ref "MOTOR1") (pin "28") (pinfunction "28_28") (pintype "passive"))
    )
    (net (code "22") (name "/M1QA-2") (class "Default")
      (node (ref "JP1") (pin "3") (pinfunction "3_3") (pintype "passive"))
      (node (ref "MOTOR2") (pin "28") (pinfunction "28_28") (pintype "passive"))
    )
    (net (code "23") (name "/M1QA-3") (class "Default")
      (node (ref "JP2") (pin "3") (pinfunction "3_3") (pintype "passive"))
      (node (ref "MOTOR3") (pin "28") (pinfunction "28_28") (pintype "passive"))
    )
    (net (code "24") (name "/M1QA-4") (class "Default")
      (node (ref "JP3") (pin "3") (pinfunction "3_3") (pintype "passive"))
      (node (ref "MOTOR4") (pin "28") (pinfunction "28_28") (pintype "passive"))
    )
    (net (code "25") (name "/M1QB-1") (class "Default")
      (node (ref "JP4") (pin "1") (pinfunction "1_1") (pintype "passive"))
      (node (ref "MOTOR1") (pin "32") (pinfunction "32_32") (pintype "passive"))
    )
    (net (code "26") (name "/M1QB-2") (class "Default")
      (node (ref "JP1") (pin "1") (pinfunction "1_1") (pintype "passive"))
      (node (ref "MOTOR2") (pin "32") (pinfunction "32_32") (pintype "passive"))
    )
    (net (code "27") (name "/M1QB-3") (class "Default")
      (node (ref "JP2") (pin "1") (pinfunction "1_1") (pintype "passive"))
      (node (ref "MOTOR3") (pin "32") (pinfunction "32_32") (pintype "passive"))
    )
    (net (code "28") (name "/M1QB-4") (class "Default")
      (node (ref "JP3") (pin "1") (pinfunction "1_1") (pintype "passive"))
      (node (ref "MOTOR4") (pin "32") (pinfunction "32_32") (pintype "passive"))
    )
    (net (code "29") (name "/MISO") (class "Default")
      (node (ref "COM_BOARD") (pin "32") (pinfunction "32_32") (pintype "passive"))
      (node (ref "MOTOR1") (pin "27") (pinfunction "27_27") (pintype "passive"))
      (node (ref "MOTOR2") (pin "27") (pinfunction "27_27") (pintype "passive"))
      (node (ref "MOTOR3") (pin "27") (pinfunction "27_27") (pintype "passive"))
      (node (ref "MOTOR4") (pin "27") (pinfunction "27_27") (pintype "passive"))
    )
    (net (code "30") (name "/MOSI") (class "Default")
      (node (ref "COM_BOARD") (pin "30") (pinfunction "30_30") (pintype "passive"))
      (node (ref "MOTOR1") (pin "25") (pinfunction "25_25") (pintype "passive"))
      (node (ref "MOTOR2") (pin "25") (pinfunction "25_25") (pintype "passive"))
      (node (ref "MOTOR3") (pin "25") (pinfunction "25_25") (pintype "passive"))
      (node (ref "MOTOR4") (pin "25") (pinfunction "25_25") (pintype "passive"))
    )
    (net (code "31") (name "/SCK") (class "Default")
      (node (ref "COM_BOARD") (pin "28") (pinfunction "28_28") (pintype "passive"))
      (node (ref "MOTOR1") (pin "29") (pinfunction "29_29") (pintype "passive"))
      (node (ref "MOTOR2") (pin "29") (pinfunction "29_29") (pintype "passive"))
      (node (ref "MOTOR3") (pin "29") (pinfunction "29_29") (pintype "passive"))
      (node (ref "MOTOR4") (pin "29") (pinfunction "29_29") (pintype "passive"))
    )
    (net (code "32") (name "/SS1") (class "Default")
      (node (ref "COM_BOARD") (pin "20") (pinfunction "20_20") (pintype "passive"))
      (node (ref "MOTOR1") (pin "31") (pinfunction "31_31") (pintype "passive"))
    )
    (net (code "33") (name "/SS2") (class "Default")
      (node (ref "COM_BOARD") (pin "22") (pinfunction "22_22") (pintype "passive"))
      (node (ref "MOTOR2") (pin "31") (pinfunction "31_31") (pintype "passive"))
    )
    (net (code "34") (name "/SS3") (class "Default")
      (node (ref "COM_BOARD") (pin "24") (pinfunction "24_24") (pintype "passive"))
      (node (ref "MOTOR3") (pin "31") (pinfunction "31_31") (pintype "passive"))
    )
    (net (code "35") (name "/SS4") (class "Default")
      (node (ref "COM_BOARD") (pin "26") (pinfunction "26_26") (pintype "passive"))
      (node (ref "MOTOR4") (pin "31") (pinfunction "31_31") (pintype "passive"))
    )
    (net (code "36") (name "Net-(ANDS-A1)") (class "Default")
      (node (ref "ANDS") (pin "P$1") (pinfunction "A1_P$1") (pintype "bidirectional"))
      (node (ref "ANDS") (pin "P$5") (pinfunction "A2_P$5") (pintype "bidirectional"))
      (node (ref "CAP_COMP") (pin "4") (pinfunction "OUT_4") (pintype "output"))
      (node (ref "COMP_LED") (pin "A") (pinfunction "A_A") (pintype "passive"))
      (node (ref "R29") (pin "2") (pinfunction "2_2") (pintype "passive"))
      (node (ref "R7") (pin "1") (pinfunction "1_1") (pintype "passive"))
    )
    (net (code "37") (name "Net-(BB_CON-P$1)") (class "Default")
      (node (ref "BB_CON") (pin "1") (pinfunction "P$1_1") (pintype "bidirectional"))
      (node (ref "R20") (pin "2") (pinfunction "2_2") (pintype "passive"))
    )
    (net (code "38") (name "Net-(BB_CON-P$4)") (class "Default")
      (node (ref "BB_CON") (pin "4") (pinfunction "P$4_4") (pintype "bidirectional"))
      (node (ref "R19") (pin "2") (pinfunction "2_2") (pintype "passive"))
    )
    (net (code "39") (name "Net-(CAP_COMP-IN+)") (class "Default")
      (node (ref "CAP_COMP") (pin "1") (pinfunction "IN+_1") (pintype "input"))
      (node (ref "R7") (pin "2") (pinfunction "2_2") (pintype "passive"))
      (node (ref "R8") (pin "1") (pinfunction "1_1") (pintype "passive"))
    )
    (net (code "40") (name "Net-(CAP_SENSE_BUF-+IN)") (class "Default")
      (node (ref "CAP_SENSE_BUF") (pin "3") (pinfunction "+IN_3") (pintype "input"))
      (node (ref "CLAMP1") (pin "A") (pinfunction "A_A") (pintype "passive"))
      (node (ref "CLAMP2") (pin "C") (pinfunction "C_C") (pintype "passive"))
      (node (ref "R14") (pin "1") (pinfunction "1_1") (pintype "passive"))
      (node (ref "R15") (pin "2") (pinfunction "2_2") (pintype "passive"))
    )
    (net (code "41") (name "Net-(CE_LED-PadC)") (class "Default")
      (node (ref "CE_LED") (pin "C") (pinfunction "C_C") (pintype "passive"))
      (node (ref "R5") (pin "1") (pinfunction "1_1") (pintype "passive"))
    )
    (net (code "42") (name "Net-(CHARGE_D-PadA)") (class "Default")
      (node (ref "CHARGE_D") (pin "A") (pinfunction "A_A") (pintype "passive"))
      (node (ref "U$3") (pin "P$1") (pinfunction "P$1_P$1") (pintype "bidirectional"))
    )
    (net (code "43") (name "Net-(CHARGE_LED-PadC)") (class "Default")
      (node (ref "CHARGE_LED") (pin "C") (pinfunction "C_C") (pintype "passive"))
      (node (ref "R11") (pin "1") (pinfunction "1_1") (pintype "passive"))
    )
    (net (code "44") (name "Net-(CHARGE_U-GATE)") (class "Default")
      (node (ref "CHARGE_U") (pin "P$7") (pinfunction "GATE_P$7") (pintype "bidirectional"))
      (node (ref "GATE_TEST") (pin "P$1") (pinfunction "P$1_P$1") (pintype "bidirectional"))
      (node (ref "SWITCH_Q") (pin "GATE") (pinfunction "G_GATE") (pintype "bidirectional"))
    )
    (net (code "45") (name "Net-(CHARGE_U-RBG)") (class "Default")
      (node (ref "C19") (pin "1") (pinfunction "1_1") (pintype "passive"))
      (node (ref "CHARGE_U") (pin "P$10") (pinfunction "RBG_P$10") (pintype "bidirectional"))
      (node (ref "RBG") (pin "2") (pinfunction "2_2") (pintype "passive"))
    )
    (net (code "46") (name "Net-(CHARGE_U-RDCM)") (class "Default")
      (node (ref "CHARGE_U") (pin "P$8") (pinfunction "RDCM_P$8") (pintype "bidirectional"))
      (node (ref "R31") (pin "1") (pinfunction "1_1") (pintype "passive"))
    )
    (net (code "47") (name "Net-(CHARGE_U-RV)") (class "Default")
      (node (ref "CHARGE_U") (pin "P$9") (pinfunction "RV_P$9") (pintype "bidirectional"))
      (node (ref "RVOUT") (pin "1") (pinfunction "1_1") (pintype "passive"))
    )
    (net (code "48") (name "Net-(CHARGE_U-SRC)") (class "Default")
      (node (ref "CHARGE_U") (pin "P$6") (pinfunction "SRC_P$6") (pintype "bidirectional"))
      (node (ref "RSENSE") (pin "2") (pinfunction "2_2") (pintype "passive"))
      (node (ref "SWITCH_Q") (pin "SOURCE") (pinfunction "S_SOURCE") (pintype "bidirectional"))
    )
    (net (code "49") (name "Net-(CHIP-P$2)") (class "Default")
      (node (ref "CHIP") (pin "2") (pinfunction "P$2_2") (pintype "bidirectional"))
      (node (ref "CHIP_FLY") (pin "ANODE") (pinfunction "A_ANODE") (pintype "passive"))
      (node (ref "KICK_Q1") (pin "DRAIN") (pinfunction "D_DRAIN") (pintype "bidirectional"))
    )
    (net (code "50") (name "Net-(CHIP_LED-PadC)") (class "Default")
      (node (ref "CHIP_LED") (pin "C") (pinfunction "C_C") (pintype "passive"))
      (node (ref "R10") (pin "2") (pinfunction "2_2") (pintype "passive"))
    )
    (net (code "51") (name "Net-(COMP_LED-PadC)") (class "Default")
      (node (ref "COMP_LED") (pin "C") (pinfunction "C_C") (pintype "passive"))
      (node (ref "R6") (pin "2") (pinfunction "2_2") (pintype "passive"))
    )
    (net (code "52") (name "Net-(COMS_BOARD_FUSE-Pad2)") (class "Default")
      (node (ref "COMS_BOARD_FUSE") (pin "2") (pinfunction "2_2") (pintype "passive"))
      (node (ref "COM_BOARD") (pin "1") (pinfunction "1_1") (pintype "passive"))
      (node (ref "COM_BOARD") (pin "3") (pinfunction "3_3") (pintype "passive"))
      (node (ref "COM_BOARD") (pin "5") (pinfunction "5_5") (pintype "passive"))
    )
    (net (code "53") (name "Net-(DONE_LED-PadC)") (class "Default")
      (node (ref "DONE_LED") (pin "C") (pinfunction "C_C") (pintype "passive"))
      (node (ref "R12") (pin "1") (pinfunction "1_1") (pintype "passive"))
    )
    (net (code "54") (name "Net-(DRIB-P$2)") (class "Default")
      (node (ref "DRIB") (pin "2") (pinfunction "P$2_2") (pintype "bidirectional"))
      (node (ref "DRIB_TRAN") (pin "DRAIN") (pinfunction "D_DRAIN") (pintype "bidirectional"))
    )
    (net (code "55") (name "Net-(FUSE_MOTOR_3-Pad2)") (class "Default")
      (node (ref "FUSE_MOTOR_3") (pin "2") (pinfunction "2_2") (pintype "passive"))
      (node (ref "MOTOR1") (pin "1") (pinfunction "1_1") (pintype "passive"))
      (node (ref "MOTOR1") (pin "2") (pinfunction "2_2") (pintype "passive"))
      (node (ref "MOTOR1") (pin "3") (pinfunction "3_3") (pintype "passive"))
      (node (ref "MOTOR1") (pin "4") (pinfunction "4_4") (pintype "passive"))
      (node (ref "MOTOR1") (pin "5") (pinfunction "5_5") (pintype "passive"))
      (node (ref "MOTOR1") (pin "6") (pinfunction "6_6") (pintype "passive"))
    )
    (net (code "56") (name "Net-(FUSE_MOTOR_5-Pad2)") (class "Default")
      (node (ref "FUSE_MOTOR_5") (pin "2") (pinfunction "2_2") (pintype "passive"))
      (node (ref "MOTOR2") (pin "1") (pinfunction "1_1") (pintype "passive"))
      (node (ref "MOTOR2") (pin "2") (pinfunction "2_2") (pintype "passive"))
      (node (ref "MOTOR2") (pin "3") (pinfunction "3_3") (pintype "passive"))
      (node (ref "MOTOR2") (pin "4") (pinfunction "4_4") (pintype "passive"))
      (node (ref "MOTOR2") (pin "5") (pinfunction "5_5") (pintype "passive"))
      (node (ref "MOTOR2") (pin "6") (pinfunction "6_6") (pintype "passive"))
    )
    (net (code "57") (name "Net-(FUSE_MOTOR_6-Pad2)") (class "Default")
      (node (ref "FUSE_MOTOR_6") (pin "2") (pinfunction "2_2") (pintype "passive"))
      (node (ref "MOTOR3") (pin "1") (pinfunction "1_1") (pintype "passive"))
      (node (ref "MOTOR3") (pin "2") (pinfunction "2_2") (pintype "passive"))
      (node (ref "MOTOR3") (pin "3") (pinfunction "3_3") (pintype "passive"))
      (node (ref "MOTOR3") (pin "4") (pinfunction "4_4") (pintype "passive"))
      (node (ref "MOTOR3") (pin "5") (pinfunction "5_5") (pintype "passive"))
      (node (ref "MOTOR3") (pin "6") (pinfunction "6_6") (pintype "passive"))
    )
    (net (code "58") (name "Net-(FUSE_MOTOR_7-Pad2)") (class "Default")
      (node (ref "FUSE_MOTOR_7") (pin "2") (pinfunction "2_2") (pintype "passive"))
      (node (ref "MOTOR4") (pin "1") (pinfunction "1_1") (pintype "passive"))
      (node (ref "MOTOR4") (pin "2") (pinfunction "2_2") (pintype "passive"))
      (node (ref "MOTOR4") (pin "3") (pinfunction "3_3") (pintype "passive"))
      (node (ref "MOTOR4") (pin "4") (pinfunction "4_4") (pintype "passive"))
      (node (ref "MOTOR4") (pin "5") (pinfunction "5_5") (pintype "passive"))
      (node (ref "MOTOR4") (pin "6") (pinfunction "6_6") (pintype "passive"))
    )
    (net (code "59") (name "Net-(KE_LED-PadC)") (class "Default")
      (node (ref "KE_LED") (pin "C") (pinfunction "C_C") (pintype "passive"))
      (node (ref "R4") (pin "1") (pinfunction "1_1") (pintype "passive"))
    )
    (net (code "60") (name "Net-(KICK-P$2)") (class "Default")
      (node (ref "KICK") (pin "2") (pinfunction "P$2_2") (pintype "bidirectional"))
      (node (ref "KICK_FLY") (pin "ANODE") (pinfunction "A_ANODE") (pintype "passive"))
      (node (ref "KICK_Q") (pin "DRAIN") (pinfunction "D_DRAIN") (pintype "bidirectional"))
    )
    (net (code "61") (name "Net-(KICK_LED-PadC)") (class "Default")
      (node (ref "KICK_LED") (pin "C") (pinfunction "C_C") (pintype "passive"))
      (node (ref "R9") (pin "2") (pinfunction "2_2") (pintype "passive"))
    )
    (net (code "62") (name "Net-(KICK_Q-G)") (class "Default")
      (node (ref "KICK_Q") (pin "GATE") (pinfunction "G_GATE") (pintype "bidirectional"))
      (node (ref "R1") (pin "2") (pinfunction "2_2") (pintype "passive"))
    )
    (net (code "63") (name "Net-(KICK_Q1-G)") (class "Default")
      (node (ref "KICK_Q1") (pin "GATE") (pinfunction "G_GATE") (pintype "bidirectional"))
      (node (ref "R2") (pin "2") (pinfunction "2_2") (pintype "passive"))
    )
    (net (code "64") (name "Net-(NEON-Pad1)") (class "Default")
      (node (ref "NEON") (pin "1") (pinfunction "1_1") (pintype "passive"))
      (node (ref "R24") (pin "1") (pinfunction "1_1") (pintype "passive"))
    )
    (net (code "65") (name "Net-(PW_LED1-PadC)") (class "Default")
      (node (ref "PW_LED1") (pin "C") (pinfunction "C_C") (pintype "passive"))
      (node (ref "R21") (pin "2") (pinfunction "2_2") (pintype "passive"))
    )
    (net (code "66") (name "Net-(SWITCH_Q-D)") (class "Default")
      (node (ref "DRAIN_TEST") (pin "P$1") (pinfunction "P$1_P$1") (pintype "bidirectional"))
      (node (ref "R31") (pin "2") (pinfunction "2_2") (pintype "passive"))
      (node (ref "RVOUT") (pin "2") (pinfunction "2_2") (pintype "passive"))
      (node (ref "SWITCH_Q") (pin "DRAIN") (pinfunction "D_DRAIN") (pintype "bidirectional"))
      (node (ref "U$3") (pin "P$6") (pinfunction "P$6_P$6") (pintype "bidirectional"))
      (node (ref "U$3") (pin "P$7") (pinfunction "P$7_P$7") (pintype "bidirectional"))
    )
    (net (code "67") (name "Net-(U$1-OUT)") (class "Default")
      (node (ref "R2") (pin "1") (pinfunction "1_1") (pintype "passive"))
      (node (ref "U$1") (pin "5") (pinfunction "OUT_5") (pintype "output"))
    )
    (net (code "68") (name "Net-(U$2-DRAIN)") (class "Default")
      (node (ref "U$2") (pin "TAB") (pinfunction "DRAIN_TAB") (pintype "bidirectional"))
      (node (ref "U$7") (pin "-") (pinfunction "D-_-") (pintype "bidirectional"))
    )
    (net (code "69") (name "Net-(U$2-GATE)") (class "Default")
      (node (ref "R25") (pin "1") (pinfunction "1_1") (pintype "passive"))
      (node (ref "U$2") (pin "LOWER_LEFT") (pinfunction "GATE_LOWER_LEFT") (pintype "bidirectional"))
    )
    (net (code "70") (name "Net-(U$2-SOURCE)") (class "Default")
      (node (ref "R3") (pin "1") (pinfunction "1_1") (pintype "passive"))
      (node (ref "U$2") (pin "LOWER_RIGHT") (pinfunction "SOURCE_LOWER_RIGHT") (pintype "bidirectional"))
      (node (ref "U$6") (pin "RIGHT") (pinfunction "EMITTER_RIGHT") (pintype "bidirectional"))
    )
    (net (code "71") (name "Net-(U$4-OUT)") (class "Default")
      (node (ref "R1") (pin "1") (pinfunction "1_1") (pintype "passive"))
      (node (ref "U$4") (pin "5") (pinfunction "OUT_5") (pintype "output"))
    )
    (net (code "72") (name "Net-(U$5-LED+)") (class "Default")
      (node (ref "R26") (pin "2") (pinfunction "2_2") (pintype "passive"))
      (node (ref "U$5") (pin "1") (pinfunction "LED+_1") (pintype "bidirectional"))
    )
    (net (code "73") (name "Net-(U$5-S1)") (class "Default")
      (node (ref "R16") (pin "1") (pinfunction "1_1") (pintype "passive"))
      (node (ref "R23") (pin "2") (pinfunction "2_2") (pintype "passive"))
      (node (ref "U$5") (pin "4") (pinfunction "S1_4") (pintype "bidirectional"))
    )
    (net (code "74") (name "Net-(U$6-BASE)") (class "Default")
      (node (ref "R13") (pin "1") (pinfunction "1_1") (pintype "passive"))
      (node (ref "R16") (pin "2") (pinfunction "2_2") (pintype "passive"))
      (node (ref "R3") (pin "2") (pinfunction "2_2") (pintype "passive"))
      (node (ref "U$6") (pin "CENTER") (pinfunction "BASE_CENTER") (pintype "bidirectional"))
    )
    (net (code "75") (name "Net-(U$8-P$1)") (class "Default")
      (node (ref "MOTOR2") (pin "10") (pinfunction "10_10") (pintype "passive"))
      (node (ref "MOTOR2") (pin "7") (pinfunction "7_7") (pintype "passive"))
      (node (ref "MOTOR2") (pin "8") (pinfunction "8_8") (pintype "passive"))
      (node (ref "MOTOR2") (pin "9") (pinfunction "9_9") (pintype "passive"))
      (node (ref "U$8") (pin "10") (pinfunction "P$2_10") (pintype "bidirectional"))
      (node (ref "U$8") (pin "11") (pinfunction "P$1_11") (pintype "bidirectional"))
    )
    (net (code "76") (name "Net-(U$8-P$3)") (class "Default")
      (node (ref "MOTOR2") (pin "11") (pinfunction "11_11") (pintype "passive"))
      (node (ref "MOTOR2") (pin "12") (pinfunction "12_12") (pintype "passive"))
      (node (ref "MOTOR2") (pin "13") (pinfunction "13_13") (pintype "passive"))
      (node (ref "MOTOR2") (pin "14") (pinfunction "14_14") (pintype "passive"))
      (node (ref "U$8") (pin "8") (pinfunction "P$4_8") (pintype "bidirectional"))
      (node (ref "U$8") (pin "9") (pinfunction "P$3_9") (pintype "bidirectional"))
    )
    (net (code "77") (name "Net-(U$8-P$5)") (class "Default")
      (node (ref "MOTOR2") (pin "15") (pinfunction "15_15") (pintype "passive"))
      (node (ref "MOTOR2") (pin "16") (pinfunction "16_16") (pintype "passive"))
      (node (ref "MOTOR2") (pin "17") (pinfunction "17_17") (pintype "passive"))
      (node (ref "MOTOR2") (pin "18") (pinfunction "18_18") (pintype "passive"))
      (node (ref "U$8") (pin "6") (pinfunction "P$6_6") (pintype "bidirectional"))
      (node (ref "U$8") (pin "7") (pinfunction "P$5_7") (pintype "bidirectional"))
    )
    (net (code "78") (name "Net-(U$8-P$8)") (class "Default")
      (node (ref "MOTOR2") (pin "20") (pinfunction "20_20") (pintype "passive"))
      (node (ref "U$8") (pin "4") (pinfunction "P$8_4") (pintype "bidirectional"))
    )
    (net (code "79") (name "Net-(U$8-P$9)") (class "Default")
      (node (ref "MOTOR2") (pin "19") (pinfunction "19_19") (pintype "passive"))
      (node (ref "U$8") (pin "3") (pinfunction "P$9_3") (pintype "bidirectional"))
    )
    (net (code "80") (name "Net-(U$8-P$10)") (class "Default")
      (node (ref "MOTOR2") (pin "21") (pinfunction "21_21") (pintype "passive"))
      (node (ref "U$8") (pin "2") (pinfunction "P$10_2") (pintype "bidirectional"))
    )
    (net (code "81") (name "Net-(U$8-P$11)") (class "Default")
      (node (ref "MOTOR2") (pin "23") (pinfunction "23_23") (pintype "passive"))
      (node (ref "U$8") (pin "1") (pinfunction "P$11_1") (pintype "bidirectional"))
    )
    (net (code "82") (name "Net-(U$9-P$1)") (class "Default")
      (node (ref "MOTOR3") (pin "10") (pinfunction "10_10") (pintype "passive"))
      (node (ref "MOTOR3") (pin "7") (pinfunction "7_7") (pintype "passive"))
      (node (ref "MOTOR3") (pin "8") (pinfunction "8_8") (pintype "passive"))
      (node (ref "MOTOR3") (pin "9") (pinfunction "9_9") (pintype "passive"))
      (node (ref "U$9") (pin "10") (pinfunction "P$2_10") (pintype "bidirectional"))
      (node (ref "U$9") (pin "11") (pinfunction "P$1_11") (pintype "bidirectional"))
    )
    (net (code "83") (name "Net-(U$9-P$3)") (class "Default")
      (node (ref "MOTOR3") (pin "11") (pinfunction "11_11") (pintype "passive"))
      (node (ref "MOTOR3") (pin "12") (pinfunction "12_12") (pintype "passive"))
      (node (ref "MOTOR3") (pin "13") (pinfunction "13_13") (pintype "passive"))
      (node (ref "MOTOR3") (pin "14") (pinfunction "14_14") (pintype "passive"))
      (node (ref "U$9") (pin "8") (pinfunction "P$4_8") (pintype "bidirectional"))
      (node (ref "U$9") (pin "9") (pinfunction "P$3_9") (pintype "bidirectional"))
    )
    (net (code "84") (name "Net-(U$9-P$5)") (class "Default")
      (node (ref "MOTOR3") (pin "15") (pinfunction "15_15") (pintype "passive"))
      (node (ref "MOTOR3") (pin "16") (pinfunction "16_16") (pintype "passive"))
      (node (ref "MOTOR3") (pin "17") (pinfunction "17_17") (pintype "passive"))
      (node (ref "MOTOR3") (pin "18") (pinfunction "18_18") (pintype "passive"))
      (node (ref "U$9") (pin "6") (pinfunction "P$6_6") (pintype "bidirectional"))
      (node (ref "U$9") (pin "7") (pinfunction "P$5_7") (pintype "bidirectional"))
    )
    (net (code "85") (name "Net-(U$9-P$8)") (class "Default")
      (node (ref "MOTOR3") (pin "20") (pinfunction "20_20") (pintype "passive"))
      (node (ref "U$9") (pin "4") (pinfunction "P$8_4") (pintype "bidirectional"))
    )
    (net (code "86") (name "Net-(U$9-P$9)") (class "Default")
      (node (ref "MOTOR3") (pin "19") (pinfunction "19_19") (pintype "passive"))
      (node (ref "U$9") (pin "3") (pinfunction "P$9_3") (pintype "bidirectional"))
    )
    (net (code "87") (name "Net-(U$9-P$10)") (class "Default")
      (node (ref "MOTOR3") (pin "21") (pinfunction "21_21") (pintype "passive"))
      (node (ref "U$9") (pin "2") (pinfunction "P$10_2") (pintype "bidirectional"))
    )
    (net (code "88") (name "Net-(U$9-P$11)") (class "Default")
      (node (ref "MOTOR3") (pin "23") (pinfunction "23_23") (pintype "passive"))
      (node (ref "U$9") (pin "1") (pinfunction "P$11_1") (pintype "bidirectional"))
    )
    (net (code "89") (name "Net-(U$10-P$1)") (class "Default")
      (node (ref "MOTOR4") (pin "10") (pinfunction "10_10") (pintype "passive"))
      (node (ref "MOTOR4") (pin "7") (pinfunction "7_7") (pintype "passive"))
      (node (ref "MOTOR4") (pin "8") (pinfunction "8_8") (pintype "passive"))
      (node (ref "MOTOR4") (pin "9") (pinfunction "9_9") (pintype "passive"))
      (node (ref "U$10") (pin "10") (pinfunction "P$2_10") (pintype "bidirectional"))
      (node (ref "U$10") (pin "11") (pinfunction "P$1_11") (pintype "bidirectional"))
    )
    (net (code "90") (name "Net-(U$10-P$3)") (class "Default")
      (node (ref "MOTOR4") (pin "11") (pinfunction "11_11") (pintype "passive"))
      (node (ref "MOTOR4") (pin "12") (pinfunction "12_12") (pintype "passive"))
      (node (ref "MOTOR4") (pin "13") (pinfunction "13_13") (pintype "passive"))
      (node (ref "MOTOR4") (pin "14") (pinfunction "14_14") (pintype "passive"))
      (node (ref "U$10") (pin "8") (pinfunction "P$4_8") (pintype "bidirectional"))
      (node (ref "U$10") (pin "9") (pinfunction "P$3_9") (pintype "bidirectional"))
    )
    (net (code "91") (name "Net-(U$10-P$5)") (class "Default")
      (node (ref "MOTOR4") (pin "15") (pinfunction "15_15") (pintype "passive"))
      (node (ref "MOTOR4") (pin "16") (pinfunction "16_16") (pintype "passive"))
      (node (ref "MOTOR4") (pin "17") (pinfunction "17_17") (pintype "passive"))
      (node (ref "MOTOR4") (pin "18") (pinfunction "18_18") (pintype "passive"))
      (node (ref "U$10") (pin "6") (pinfunction "P$6_6") (pintype "bidirectional"))
      (node (ref "U$10") (pin "7") (pinfunction "P$5_7") (pintype "bidirectional"))
    )
    (net (code "92") (name "Net-(U$10-P$8)") (class "Default")
      (node (ref "MOTOR4") (pin "20") (pinfunction "20_20") (pintype "passive"))
      (node (ref "U$10") (pin "4") (pinfunction "P$8_4") (pintype "bidirectional"))
    )
    (net (code "93") (name "Net-(U$10-P$9)") (class "Default")
      (node (ref "MOTOR4") (pin "19") (pinfunction "19_19") (pintype "passive"))
      (node (ref "U$10") (pin "3") (pinfunction "P$9_3") (pintype "bidirectional"))
    )
    (net (code "94") (name "Net-(U$10-P$10)") (class "Default")
      (node (ref "MOTOR4") (pin "21") (pinfunction "21_21") (pintype "passive"))
      (node (ref "U$10") (pin "2") (pinfunction "P$10_2") (pintype "bidirectional"))
    )
    (net (code "95") (name "Net-(U$10-P$11)") (class "Default")
      (node (ref "MOTOR4") (pin "23") (pinfunction "23_23") (pintype "passive"))
      (node (ref "U$10") (pin "1") (pinfunction "P$11_1") (pintype "bidirectional"))
    )
    (net (code "96") (name "Net-(U$11-P$1)") (class "Default")
      (node (ref "MOTOR1") (pin "10") (pinfunction "10_10") (pintype "passive"))
      (node (ref "MOTOR1") (pin "7") (pinfunction "7_7") (pintype "passive"))
      (node (ref "MOTOR1") (pin "8") (pinfunction "8_8") (pintype "passive"))
      (node (ref "MOTOR1") (pin "9") (pinfunction "9_9") (pintype "passive"))
      (node (ref "U$11") (pin "10") (pinfunction "P$2_10") (pintype "bidirectional"))
      (node (ref "U$11") (pin "11") (pinfunction "P$1_11") (pintype "bidirectional"))
    )
    (net (code "97") (name "Net-(U$11-P$3)") (class "Default")
      (node (ref "MOTOR1") (pin "11") (pinfunction "11_11") (pintype "passive"))
      (node (ref "MOTOR1") (pin "12") (pinfunction "12_12") (pintype "passive"))
      (node (ref "MOTOR1") (pin "13") (pinfunction "13_13") (pintype "passive"))
      (node (ref "MOTOR1") (pin "14") (pinfunction "14_14") (pintype "passive"))
      (node (ref "U$11") (pin "8") (pinfunction "P$4_8") (pintype "bidirectional"))
      (node (ref "U$11") (pin "9") (pinfunction "P$3_9") (pintype "bidirectional"))
    )
    (net (code "98") (name "Net-(U$11-P$5)") (class "Default")
      (node (ref "MOTOR1") (pin "15") (pinfunction "15_15") (pintype "passive"))
      (node (ref "MOTOR1") (pin "16") (pinfunction "16_16") (pintype "passive"))
      (node (ref "MOTOR1") (pin "17") (pinfunction "17_17") (pintype "passive"))
      (node (ref "MOTOR1") (pin "18") (pinfunction "18_18") (pintype "passive"))
      (node (ref "U$11") (pin "6") (pinfunction "P$6_6") (pintype "bidirectional"))
      (node (ref "U$11") (pin "7") (pinfunction "P$5_7") (pintype "bidirectional"))
    )
    (net (code "99") (name "Net-(U$11-P$8)") (class "Default")
      (node (ref "MOTOR1") (pin "20") (pinfunction "20_20") (pintype "passive"))
      (node (ref "U$11") (pin "4") (pinfunction "P$8_4") (pintype "bidirectional"))
    )
    (net (code "100") (name "Net-(U$11-P$9)") (class "Default")
      (node (ref "MOTOR1") (pin "19") (pinfunction "19_19") (pintype "passive"))
      (node (ref "U$11") (pin "3") (pinfunction "P$9_3") (pintype "bidirectional"))
    )
    (net (code "101") (name "Net-(U$11-P$10)") (class "Default")
      (node (ref "MOTOR1") (pin "21") (pinfunction "21_21") (pintype "passive"))
      (node (ref "U$11") (pin "2") (pinfunction "P$10_2") (pintype "bidirectional"))
    )
    (net (code "102") (name "Net-(U$11-P$11)") (class "Default")
      (node (ref "MOTOR1") (pin "23") (pinfunction "23_23") (pintype "passive"))
      (node (ref "U$11") (pin "1") (pinfunction "P$11_1") (pintype "bidirectional"))
    )
    (net (code "103") (name "unconnected-(COM_BOARD-Pad2)") (class "Default")
      (node (ref "COM_BOARD") (pin "2") (pinfunction "2_2") (pintype "passive"))
    )
    (net (code "104") (name "unconnected-(COM_BOARD-Pad4)") (class "Default")
      (node (ref "COM_BOARD") (pin "4") (pinfunction "4_4") (pintype "passive"))
    )
    (net (code "105") (name "unconnected-(COM_BOARD-Pad6)") (class "Default")
      (node (ref "COM_BOARD") (pin "6") (pinfunction "6_6") (pintype "passive"))
    )
    (net (code "106") (name "unconnected-(COM_BOARD-Pad8)") (class "Default")
      (node (ref "COM_BOARD") (pin "8") (pinfunction "8_8") (pintype "passive"))
    )
    (net (code "107") (name "unconnected-(COM_BOARD-Pad10)") (class "Default")
      (node (ref "COM_BOARD") (pin "10") (pinfunction "10_10") (pintype "passive"))
    )
    (net (code "108") (name "unconnected-(COM_BOARD-Pad12)") (class "Default")
      (node (ref "COM_BOARD") (pin "12") (pinfunction "12_12") (pintype "passive"))
    )
    (net (code "109") (name "unconnected-(COM_BOARD-Pad21)") (class "Default")
      (node (ref "COM_BOARD") (pin "21") (pinfunction "21_21") (pintype "passive"))
    )
    (net (code "110") (name "unconnected-(COM_BOARD-Pad23)") (class "Default")
      (node (ref "COM_BOARD") (pin "23") (pinfunction "23_23") (pintype "passive"))
    )
    (net (code "111") (name "unconnected-(COM_BOARD-Pad25)") (class "Default")
      (node (ref "COM_BOARD") (pin "25") (pinfunction "25_25") (pintype "passive"))
    )
    (net (code "112") (name "unconnected-(COM_BOARD-Pad27)") (class "Default")
      (node (ref "COM_BOARD") (pin "27") (pinfunction "27_27") (pintype "passive"))
    )
    (net (code "113") (name "unconnected-(COM_BOARD-Pad29)") (class "Default")
      (node (ref "COM_BOARD") (pin "29") (pinfunction "29_29") (pintype "passive"))
    )
    (net (code "114") (name "unconnected-(COM_BOARD-Pad31)") (class "Default")
      (node (ref "COM_BOARD") (pin "31") (pinfunction "31_31") (pintype "passive"))
    )
    (net (code "115") (name "unconnected-(MOTOR1-Pad24)") (class "Default")
      (node (ref "MOTOR1") (pin "24") (pinfunction "24_24") (pintype "passive"))
    )
    (net (code "116") (name "unconnected-(MOTOR2-Pad24)") (class "Default")
      (node (ref "MOTOR2") (pin "24") (pinfunction "24_24") (pintype "passive"))
    )
    (net (code "117") (name "unconnected-(MOTOR3-Pad24)") (class "Default")
      (node (ref "MOTOR3") (pin "24") (pinfunction "24_24") (pintype "passive"))
    )
    (net (code "118") (name "unconnected-(MOTOR4-Pad24)") (class "Default")
      (node (ref "MOTOR4") (pin "24") (pinfunction "24_24") (pintype "passive"))
    )
  )
)
